# BW1098OBC_LEFT_OV9282.net
KiCad netlist of a schematic drawn in Altium Designer
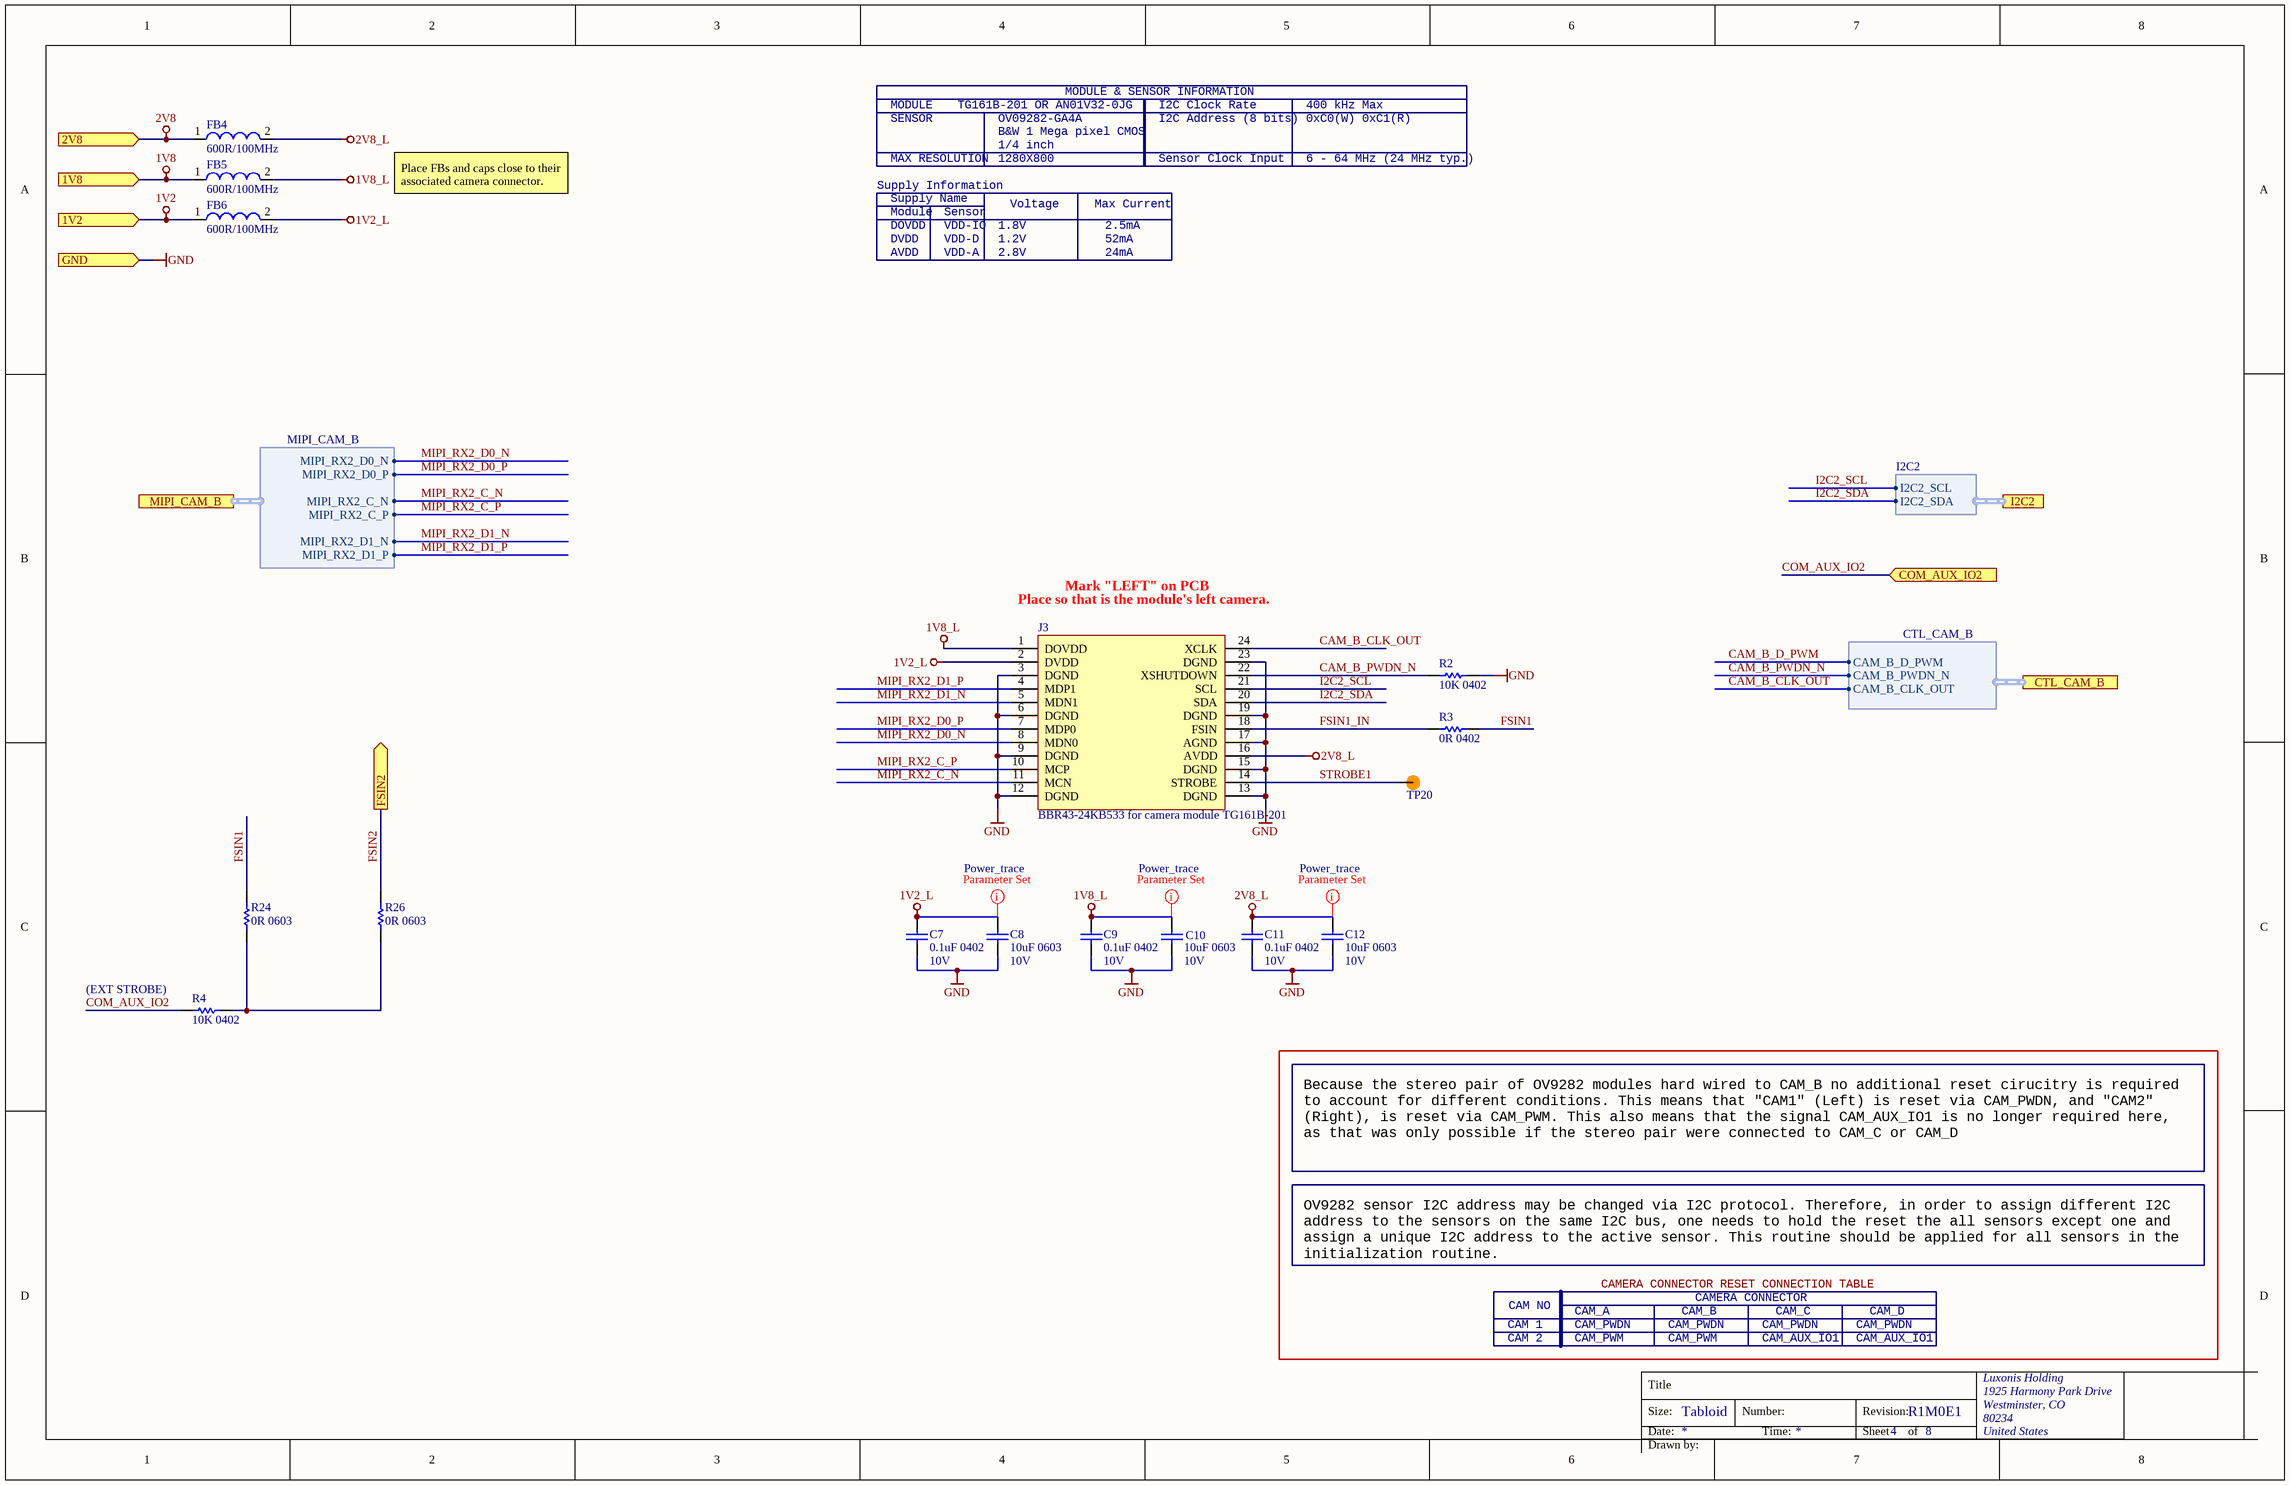
[diagram p0: BW1098OBC_LEFT_OV9282.SchDoc]

(export (version "E")
  (design (tool "Eeschema 10.0.6"))
  (components
    (comp (ref "C7")
      (value "0.1uF 0402")
      (footprint "CAP_Altium_Vault_Generic:CAPC0402(1005)70_L")
      (description "CAP CER 0.1UF 10V X7R 0402 5%")
      (fields (field (name "TOLERANCE") "5%") (field (name "VOLTAGE RATING") "10V"))
      (libsource (lib "LuxonisMaster") (part "GRM155R71A104JA01D"))
    )
    (comp (ref "C8")
      (value "10uF 0603")
      (footprint "CAP_Altium_Vault_Generic:CAPC0603(1608)100_L")
      (description "CAP CER 10UF 10V X5R 0603 20%")
      (fields (field (name "TOLERANCE") "20%") (field (name "VOLTAGE RATING") "10V"))
      (libsource (lib "LuxonisMaster") (part "GRM188R61A106ME69D"))
    )
    (comp (ref "C9")
      (value "0.1uF 0402")
      (footprint "CAP_Altium_Vault_Generic:CAPC0402(1005)70_L")
      (description "CAP CER 0.1UF 10V X7R 0402 5%")
      (fields (field (name "TOLERANCE") "5%") (field (name "VOLTAGE RATING") "10V"))
      (libsource (lib "LuxonisMaster") (part "GRM155R71A104JA01D"))
    )
    (comp (ref "C10")
      (value "10uF 0603")
      (footprint "CAP_Altium_Vault_Generic:CAPC0603(1608)100_L")
      (description "CAP CER 10UF 10V X5R 0603 20%")
      (fields (field (name "TOLERANCE") "20%") (field (name "VOLTAGE RATING") "10V"))
      (libsource (lib "LuxonisMaster") (part "GRM188R61A106ME69D"))
    )
    (comp (ref "C11")
      (value "0.1uF 0402")
      (footprint "CAP_Altium_Vault_Generic:CAPC0402(1005)70_L")
      (description "CAP CER 0.1UF 10V X7R 0402 5%")
      (fields (field (name "TOLERANCE") "5%") (field (name "VOLTAGE RATING") "10V"))
      (libsource (lib "LuxonisMaster") (part "GRM155R71A104JA01D"))
    )
    (comp (ref "C12")
      (value "10uF 0603")
      (footprint "CAP_Altium_Vault_Generic:CAPC0603(1608)100_L")
      (description "CAP CER 10UF 10V X5R 0603 20%")
      (fields (field (name "TOLERANCE") "20%") (field (name "VOLTAGE RATING") "10V"))
      (libsource (lib "LuxonisMaster") (part "GRM188R61A106ME69D"))
    )
    (comp (ref "FB4")
      (value "600R/100MHz")
      (footprint "LuxonisMaster:2508056017Y2")
      (description "FERRITE BEAD, 0.1OHM, 2A, 0805, 600R/100MHz")
      (fields (field (name "TOLERANCE") "25%"))
      (libsource (lib "LuxonisMaster") (part "2508056017Y2"))
    )
    (comp (ref "FB5")
      (value "600R/100MHz")
      (footprint "LuxonisMaster:2508056017Y2")
      (description "FERRITE BEAD, 0.1OHM, 2A, 0805, 600R/100MHz")
      (fields (field (name "TOLERANCE") "25%"))
      (libsource (lib "LuxonisMaster") (part "2508056017Y2"))
    )
    (comp (ref "FB6")
      (value "600R/100MHz")
      (footprint "LuxonisMaster:2508056017Y2")
      (description "FERRITE BEAD, 0.1OHM, 2A, 0805, 600R/100MHz")
      (fields (field (name "TOLERANCE") "25%"))
      (libsource (lib "LuxonisMaster") (part "2508056017Y2"))
    )
    (comp (ref "J3")
      (value "BBR43-24KB533 for camera module TG161B-201")
      (footprint "BW1098OBC:TG161B-201 / AN01V32 - Board Wrap (7mm setback) MinPads")
      (description "CONN 24 way, 2 row board to board connector SMD")
      (fields (field (name "MANUFACTURER") "ACON"))
      (libsource (lib "LuxonisMaster") (part "TG161B-201_Connector"))
    )
    (comp (ref "R2")
      (value "10K 0402")
      (footprint "RES_Altium_Vault_Generic:RESC0402(1005)_L")
      (fields (field (name "TOLERANCE") "1%"))
      (libsource (lib "LuxonisMaster") (part "RC0402FR-1310KL"))
    )
    (comp (ref "R3")
      (value "0R 0402")
      (footprint "RES_Altium_Vault_Generic:RESC0402(1005)_L")
      (description "RES SMD 0 OHM JUMPER 1/16W 0402")
      (fields (field (name "TOLERANCE") "5%"))
      (libsource (lib "LuxonisMaster") (part "CRCW04020000Z0ED"))
    )
    (comp (ref "R4")
      (value "10K 0402")
      (footprint "RES_Altium_Vault_Generic:RESC0402(1005)_L")
      (fields (field (name "TOLERANCE") "1%"))
      (libsource (lib "LuxonisMaster") (part "RC0402FR-1310KL"))
    )
    (comp (ref "R24")
      (value "0R 0603")
      (footprint "RES_Altium_Vault_Generic:RESC0603(1608)_N")
      (fields (field (name "TOLERANCE") "5%"))
      (libsource (lib "LuxonisMaster") (part "CRCW06030000Z0EA"))
    )
    (comp (ref "R26")
      (value "0R 0603")
      (footprint "RES_Altium_Vault_Generic:RESC0603(1608)_N")
      (fields (field (name "TOLERANCE") "5%"))
      (libsource (lib "LuxonisMaster") (part "CRCW06030000Z0EA"))
    )
    (comp (ref "TP20")
      (value "TP100_200_NS")
      (footprint "LuxonisMaster:TP100_200_NS")
      (libsource (lib "LuxonisMaster") (part "TEST_POINT"))
    )
  )
  (nets
    (net (code "4") (name "/CAM_B_CLK_OUT") (class "Default")
      (node (ref "J3") (pin "24") (pinfunction "XCLK_24") (pintype "passive"))
    )
    (net (code "6") (name "/CAM_B_PWDN_N") (class "Default")
      (node (ref "J3") (pin "22") (pinfunction "XSHUTDOWN_22") (pintype "passive"))
      (node (ref "R2") (pin "1") (pinfunction "1_1") (pintype "passive"))
    )
    (net (code "7") (name "/COM_AUX_IO2") (class "Default")
      (node (ref "R4") (pin "1") (pinfunction "1_1") (pintype "passive"))
    )
    (net (code "8") (name "/FSIN1") (class "Default")
      (node (ref "R24") (pin "2") (pinfunction "2_2") (pintype "passive"))
      (node (ref "R3") (pin "2") (pinfunction "2_2") (pintype "passive"))
    )
    (net (code "9") (name "/FSIN1_IN") (class "Default")
      (node (ref "J3") (pin "18") (pinfunction "FSIN_18") (pintype "passive"))
      (node (ref "R3") (pin "1") (pinfunction "1_1") (pintype "passive"))
    )
    (net (code "10") (name "/FSIN2") (class "Default")
      (node (ref "R26") (pin "2") (pinfunction "2_2") (pintype "passive"))
    )
    (net (code "11") (name "/I2C2_SCL") (class "Default")
      (node (ref "J3") (pin "21") (pinfunction "SCL_21") (pintype "passive"))
    )
    (net (code "12") (name "/I2C2_SDA") (class "Default")
      (node (ref "J3") (pin "20") (pinfunction "SDA_20") (pintype "passive"))
    )
    (net (code "13") (name "/MIPI_RX2_C_N") (class "Default")
      (node (ref "J3") (pin "11") (pinfunction "MCN_11") (pintype "passive"))
    )
    (net (code "14") (name "/MIPI_RX2_C_P") (class "Default")
      (node (ref "J3") (pin "10") (pinfunction "MCP_10") (pintype "passive"))
    )
    (net (code "15") (name "/MIPI_RX2_D0_N") (class "Default")
      (node (ref "J3") (pin "8") (pinfunction "MDN0_8") (pintype "passive"))
    )
    (net (code "16") (name "/MIPI_RX2_D0_P") (class "Default")
      (node (ref "J3") (pin "7") (pinfunction "MDP0_7") (pintype "passive"))
    )
    (net (code "17") (name "/MIPI_RX2_D1_N") (class "Default")
      (node (ref "J3") (pin "5") (pinfunction "MDN1_5") (pintype "passive"))
    )
    (net (code "18") (name "/MIPI_RX2_D1_P") (class "Default")
      (node (ref "J3") (pin "4") (pinfunction "MDP1_4") (pintype "passive"))
    )
    (net (code "19") (name "/STROBE1") (class "Default")
      (node (ref "J3") (pin "14") (pinfunction "STROBE_14") (pintype "passive"))
      (node (ref "TP20") (pin "1") (pintype "passive"))
    )
    (net (code "23") (name "1V2") (class "Default")
      (node (ref "FB6") (pin "1") (pinfunction "1_1") (pintype "passive"))
    )
    (net (code "24") (name "1V2_L") (class "Default")
      (node (ref "C7") (pin "2") (pinfunction "2_2") (pintype "passive"))
      (node (ref "C8") (pin "2") (pinfunction "2_2") (pintype "passive"))
      (node (ref "FB6") (pin "2") (pinfunction "2_2") (pintype "passive"))
      (node (ref "J3") (pin "2") (pinfunction "DVDD_2") (pintype "passive"))
    )
    (net (code "25") (name "1V8") (class "Default")
      (node (ref "FB5") (pin "1") (pinfunction "1_1") (pintype "passive"))
    )
    (net (code "26") (name "1V8_L") (class "Default")
      (node (ref "C10") (pin "2") (pinfunction "2_2") (pintype "passive"))
      (node (ref "C9") (pin "2") (pinfunction "2_2") (pintype "passive"))
      (node (ref "FB5") (pin "2") (pinfunction "2_2") (pintype "passive"))
      (node (ref "J3") (pin "1") (pinfunction "DOVDD_1") (pintype "passive"))
    )
    (net (code "27") (name "2V8") (class "Default")
      (node (ref "FB4") (pin "1") (pinfunction "1_1") (pintype "passive"))
    )
    (net (code "28") (name "2V8_L") (class "Default")
      (node (ref "C11") (pin "2") (pinfunction "2_2") (pintype "passive"))
      (node (ref "C12") (pin "2") (pinfunction "2_2") (pintype "passive"))
      (node (ref "FB4") (pin "2") (pinfunction "2_2") (pintype "passive"))
      (node (ref "J3") (pin "16") (pinfunction "AVDD_16") (pintype "passive"))
    )
    (net (code "29") (name "GND") (class "Default")
      (node (ref "C10") (pin "1") (pinfunction "1_1") (pintype "passive"))
      (node (ref "C11") (pin "1") (pinfunction "1_1") (pintype "passive"))
      (node (ref "C12") (pin "1") (pinfunction "1_1") (pintype "passive"))
      (node (ref "C7") (pin "1") (pinfunction "1_1") (pintype "passive"))
      (node (ref "C8") (pin "1") (pinfunction "1_1") (pintype "passive"))
      (node (ref "C9") (pin "1") (pinfunction "1_1") (pintype "passive"))
      (node (ref "J3") (pin "12") (pinfunction "DGND_12") (pintype "passive"))
      (node (ref "J3") (pin "13") (pinfunction "DGND_13") (pintype "passive"))
      (node (ref "J3") (pin "15") (pinfunction "DGND_15") (pintype "passive"))
      (node (ref "J3") (pin "17") (pinfunction "AGND_17") (pintype "passive"))
      (node (ref "J3") (pin "19") (pinfunction "DGND_19") (pintype "passive"))
      (node (ref "J3") (pin "23") (pinfunction "DGND_23") (pintype "passive"))
      (node (ref "J3") (pin "3") (pinfunction "DGND_3") (pintype "passive"))
      (node (ref "J3") (pin "6") (pinfunction "DGND_6") (pintype "passive"))
      (node (ref "J3") (pin "9") (pinfunction "DGND_9") (pintype "passive"))
      (node (ref "R2") (pin "2") (pinfunction "2_2") (pintype "passive"))
    )
    (net (code "30") (name "Net-(R24-Pad1)") (class "Default")
      (node (ref "R24") (pin "1") (pinfunction "1_1") (pintype "passive"))
      (node (ref "R26") (pin "1") (pinfunction "1_1") (pintype "passive"))
      (node (ref "R4") (pin "2") (pinfunction "2_2") (pintype "passive"))
    )
  )
)
